# SimulatorT2PowerRevD.net
KiCad netlist of a schematic drawn in EAGLE
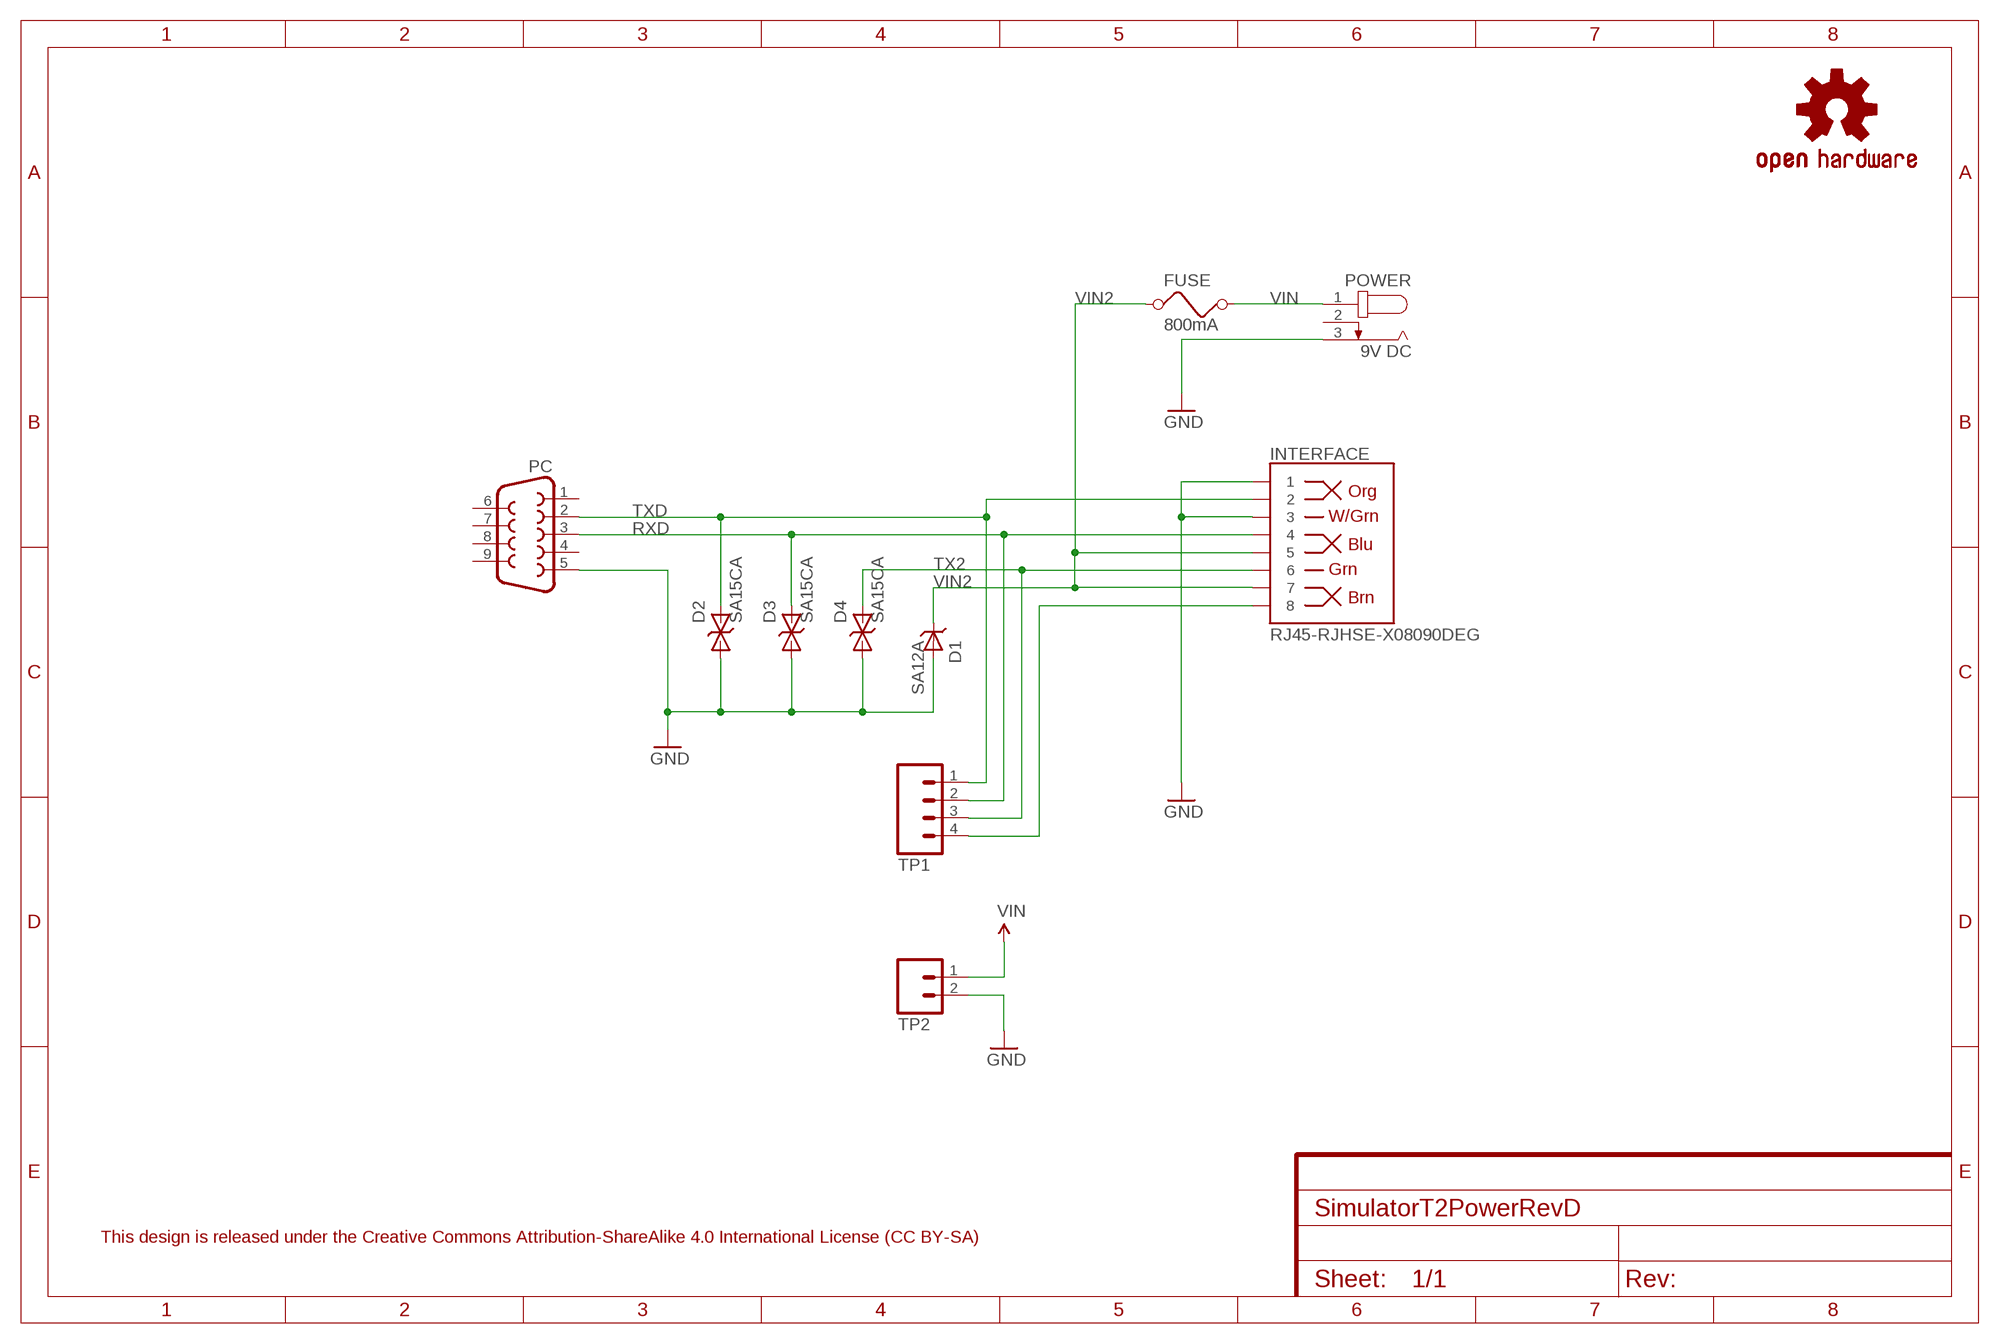
[diagram p0: schematic, sheet 1]

(export (version "E")
  (design (tool "Eeschema 10.0.6"))
  (components
    (comp (ref "D1")
      (value "SA12A")
      (footprint "eagle-import:DO41_TVS_UNI")
      (libsource (lib "eagle-import") (part "SA12A"))
    )
    (comp (ref "D2")
      (value "SA15CA")
      (footprint "eagle-import:DO41_TVS_BI")
      (libsource (lib "eagle-import") (part "SA15CA"))
    )
    (comp (ref "D3")
      (value "SA15CA")
      (footprint "eagle-import:DO41_TVS_BI")
      (libsource (lib "eagle-import") (part "SA15CA"))
    )
    (comp (ref "D4")
      (value "SA15CA")
      (footprint "eagle-import:DO41_TVS_BI")
      (libsource (lib "eagle-import") (part "SA15CA"))
    )
    (comp (ref "FUSE")
      (value "800mA")
      (footprint "eagle-import:MCOMP-FUSE-HOLDER-PCB")
      (libsource (lib "eagle-import") (part "FUSE-HOLDER-PCB"))
    )
    (comp (ref "INTERFACE")
      (value "RJ45-RJHSE-X08090DEG")
      (footprint "eagle-import:RJ45-RJHSE-5080")
      (libsource (lib "eagle-import") (part "RJ45-RJHSE-X08090DEG"))
    )
    (comp (ref "LOGO1")
      (value "OSHW-LOGOS")
      (footprint "eagle-import:OSHW-LOGO-S")
      (libsource (lib "eagle-import") (part "OSHW-LOGOS"))
    )
    (comp (ref "PC")
      (value "DB9-CONNECTOR-PCBFEMALE")
      (footprint "eagle-import:MULTICOMP-DB9-FEMALE-PCB-90DEG")
      (libsource (lib "eagle-import") (part "DB9-CONNECTOR-PCBFEMALE"))
    )
    (comp (ref "POWER")
      (value "9V DC")
      (footprint "eagle-import:CLIFF-FC681465P-DC-JACK")
      (libsource (lib "eagle-import") (part "DC-POWER-JACK-PCB"))
    )
    (comp (ref "TP1")
      (value "M04PTH")
      (footprint "eagle-import:1X04")
      (libsource (lib "eagle-import") (part "M04PTH"))
    )
    (comp (ref "TP2")
      (value "M02PTH")
      (footprint "eagle-import:1X02")
      (libsource (lib "eagle-import") (part "M02PTH"))
    )
  )
  (nets
    (net (code "1") (name "/RXD") (class "Default")
      (node (ref "D3") (pin "C") (pinfunction "C_C") (pintype "passive"))
      (node (ref "INTERFACE") (pin "4") (pinfunction "4_4") (pintype "bidirectional"))
      (node (ref "PC") (pin "3") (pinfunction "3_3") (pintype "passive"))
      (node (ref "TP1") (pin "2") (pinfunction "2_2") (pintype "passive"))
    )
    (net (code "2") (name "/TX2") (class "Default")
      (node (ref "D4") (pin "C") (pinfunction "C_C") (pintype "passive"))
      (node (ref "INTERFACE") (pin "6") (pinfunction "6_6") (pintype "bidirectional"))
      (node (ref "TP1") (pin "3") (pinfunction "3_3") (pintype "passive"))
    )
    (net (code "3") (name "/TXD") (class "Default")
      (node (ref "D2") (pin "C") (pinfunction "C_C") (pintype "passive"))
      (node (ref "INTERFACE") (pin "2") (pinfunction "2_2") (pintype "bidirectional"))
      (node (ref "PC") (pin "2") (pinfunction "2_2") (pintype "passive"))
      (node (ref "TP1") (pin "1") (pinfunction "1_1") (pintype "passive"))
    )
    (net (code "4") (name "/VIN2") (class "Default")
      (node (ref "D1") (pin "CATHODE") (pinfunction "CATHODE_CATHODE") (pintype "passive"))
      (node (ref "FUSE") (pin "1") (pinfunction "1_1") (pintype "passive"))
      (node (ref "INTERFACE") (pin "5") (pinfunction "5_5") (pintype "bidirectional"))
      (node (ref "INTERFACE") (pin "7") (pinfunction "7_7") (pintype "bidirectional"))
    )
    (net (code "5") (name "GND") (class "Default")
      (node (ref "D1") (pin "ANODE") (pinfunction "ANODE_ANODE") (pintype "passive"))
      (node (ref "D2") (pin "A") (pinfunction "A_A") (pintype "passive"))
      (node (ref "D3") (pin "A") (pinfunction "A_A") (pintype "passive"))
      (node (ref "D4") (pin "A") (pinfunction "A_A") (pintype "passive"))
      (node (ref "INTERFACE") (pin "1") (pinfunction "1_1") (pintype "bidirectional"))
      (node (ref "INTERFACE") (pin "3") (pinfunction "3_3") (pintype "bidirectional"))
      (node (ref "PC") (pin "5") (pinfunction "5_5") (pintype "passive"))
      (node (ref "POWER") (pin "3") (pinfunction "3_3") (pintype "passive"))
      (node (ref "TP2") (pin "2") (pinfunction "2_2") (pintype "passive"))
    )
    (net (code "6") (name "Net-(INTERFACE-Pad8)") (class "Default")
      (node (ref "INTERFACE") (pin "8") (pinfunction "8_8") (pintype "bidirectional"))
      (node (ref "TP1") (pin "4") (pinfunction "4_4") (pintype "passive"))
    )
    (net (code "7") (name "VIN") (class "Default")
      (node (ref "FUSE") (pin "2") (pinfunction "2_2") (pintype "passive"))
      (node (ref "POWER") (pin "1") (pinfunction "1_1") (pintype "passive"))
      (node (ref "TP2") (pin "1") (pinfunction "1_1") (pintype "passive"))
    )
    (net (code "8") (name "unconnected-(PC-Pad1)") (class "Default")
      (node (ref "PC") (pin "1") (pinfunction "1_1") (pintype "passive"))
    )
    (net (code "9") (name "unconnected-(PC-Pad4)") (class "Default")
      (node (ref "PC") (pin "4") (pinfunction "4_4") (pintype "passive"))
    )
    (net (code "10") (name "unconnected-(PC-Pad6)") (class "Default")
      (node (ref "PC") (pin "6") (pinfunction "6_6") (pintype "passive"))
    )
    (net (code "11") (name "unconnected-(PC-Pad7)") (class "Default")
      (node (ref "PC") (pin "7") (pinfunction "7_7") (pintype "passive"))
    )
    (net (code "12") (name "unconnected-(PC-Pad8)") (class "Default")
      (node (ref "PC") (pin "8") (pinfunction "8_8") (pintype "passive"))
    )
    (net (code "13") (name "unconnected-(PC-Pad9)") (class "Default")
      (node (ref "PC") (pin "9") (pinfunction "9_9") (pintype "passive"))
    )
    (net (code "14") (name "unconnected-(POWER-Pad2)") (class "Default")
      (node (ref "POWER") (pin "2") (pinfunction "2_2") (pintype "passive"))
    )
  )
)
